# Amplifier.net
KiCad netlist of a schematic drawn in Altium Designer
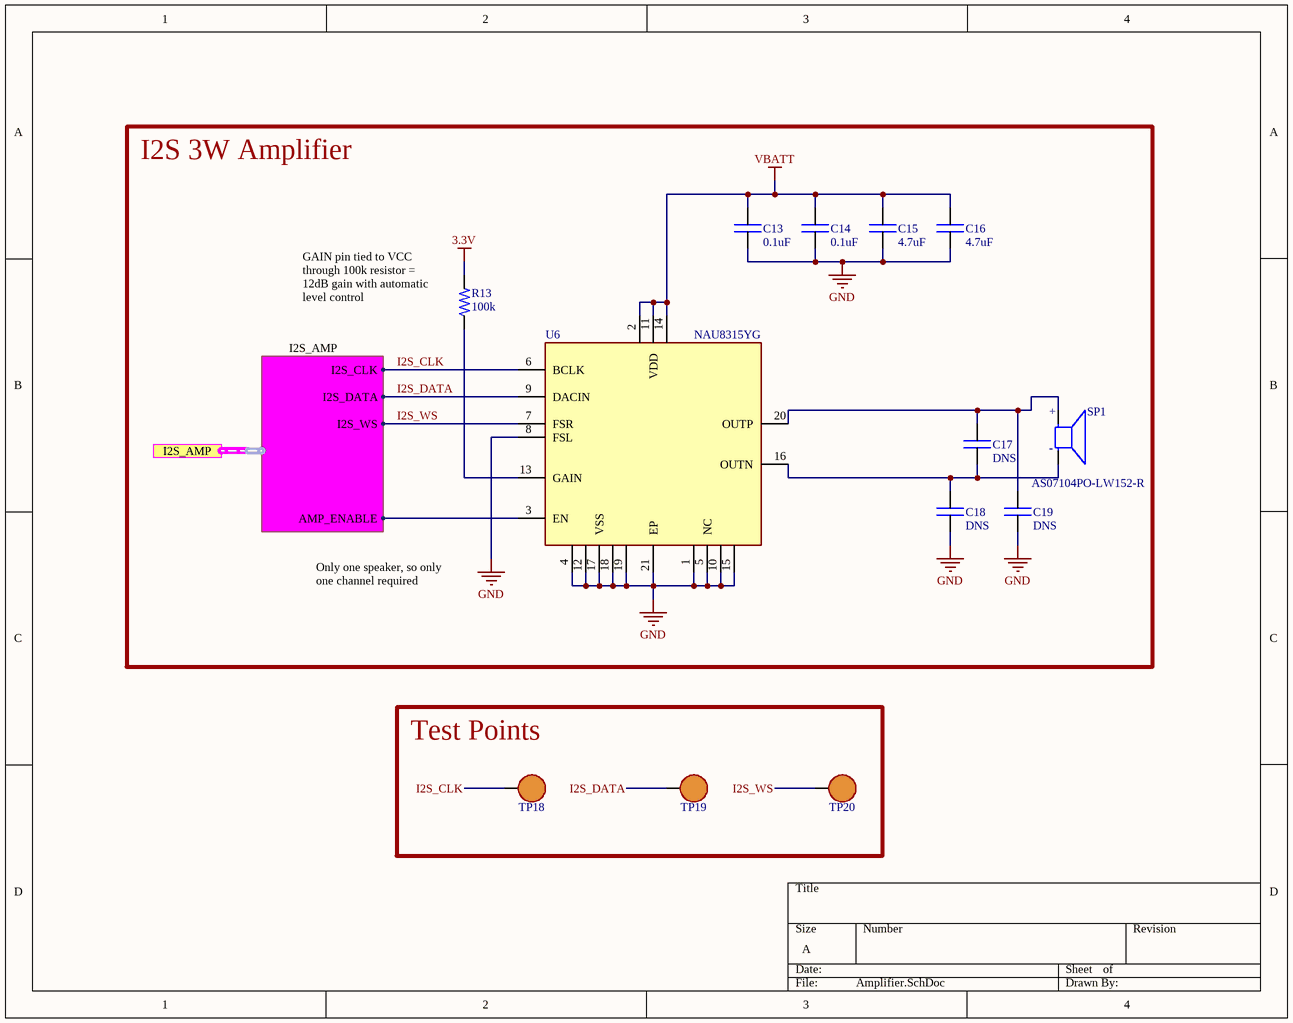
[diagram p0: Amplifier.SchDoc]

(export (version "E")
  (design (tool "Eeschema 10.0.6"))
  (components
    (comp (ref "C13")
      (value "0.1uF")
      (footprint "Christmas-2024_TSO-PCB:0402C")
      (description "Capacitor")
      (fields (field (name "MFR") "Samsung") (field (name "Comment") "CAP"))
      (libsource (lib "Christmas-2024_TSO-PCB") (part "CAP"))
    )
    (comp (ref "C14")
      (value "0.1uF")
      (footprint "Christmas-2024_TSO-PCB:0402C")
      (description "Capacitor")
      (fields (field (name "MFR") "Samsung") (field (name "Comment") "CAP"))
      (libsource (lib "Christmas-2024_TSO-PCB") (part "CAP"))
    )
    (comp (ref "C15")
      (value "4.7uF")
      (footprint "Christmas-2024_TSO-PCB:0402C")
      (description "Capacitor")
      (fields (field (name "MFR") "Samsung") (field (name "Comment") "CAP"))
      (libsource (lib "Christmas-2024_TSO-PCB") (part "CAP"))
    )
    (comp (ref "C16")
      (value "4.7uF")
      (footprint "Christmas-2024_TSO-PCB:0402C")
      (description "Capacitor")
      (fields (field (name "MFR") "Samsung") (field (name "Comment") "CAP"))
      (libsource (lib "Christmas-2024_TSO-PCB") (part "CAP"))
    )
    (comp (ref "C17")
      (value "DNS")
      (footprint "Christmas-2024_TSO-PCB:0402C")
      (description "Capacitor")
      (fields (field (name "Comment") "CAP"))
      (libsource (lib "Christmas-2024_TSO-PCB") (part "CAP"))
    )
    (comp (ref "C18")
      (value "DNS")
      (footprint "Christmas-2024_TSO-PCB:0402C")
      (description "Capacitor")
      (fields (field (name "Comment") "CAP"))
      (libsource (lib "Christmas-2024_TSO-PCB") (part "CAP"))
    )
    (comp (ref "C19")
      (value "DNS")
      (footprint "Christmas-2024_TSO-PCB:0402C")
      (description "Capacitor")
      (fields (field (name "Comment") "CAP"))
      (libsource (lib "Christmas-2024_TSO-PCB") (part "CAP"))
    )
    (comp (ref "R13")
      (value "100k")
      (footprint "Christmas-2024_TSO-PCB:0402R")
      (description "Resistor")
      (fields (field (name "MFR") "YAGEO") (field (name "Comment") "RES"))
      (libsource (lib "Christmas-2024_TSO-PCB") (part "RES"))
    )
    (comp (ref "SP1")
      (value "AS07104PO-LW152-R")
      (footprint "Christmas-2024_TSO-PCB:XMAS_26AWG_AS04004PO-2-LW152-R_SideMount")
      (description "SPEAKER 4OHM 3W TOP PORT 86DB")
      (fields (field (name "MFR") "PUI Audio, Inc."))
      (libsource (lib "Christmas-2024_TSO-PCB") (part "SPEAKER 4OHM 3W"))
    )
    (comp (ref "TP18")
      (value "RCWCTE")
      (footprint "Christmas-2024_TSO-PCB:RCWCTE")
      (description "Test Point, Surface Mount")
      (fields (field (name "MFR") "KOA Speer Electronics, Inc."))
      (libsource (lib "Christmas-2024_TSO-PCB") (part "TEST POINT"))
    )
    (comp (ref "TP19")
      (value "RCWCTE")
      (footprint "Christmas-2024_TSO-PCB:RCWCTE")
      (description "Test Point, Surface Mount")
      (fields (field (name "MFR") "KOA Speer Electronics, Inc."))
      (libsource (lib "Christmas-2024_TSO-PCB") (part "TEST POINT"))
    )
    (comp (ref "TP20")
      (value "RCWCTE")
      (footprint "Christmas-2024_TSO-PCB:RCWCTE")
      (description "Test Point, Surface Mount")
      (fields (field (name "MFR") "KOA Speer Electronics, Inc."))
      (libsource (lib "Christmas-2024_TSO-PCB") (part "TEST POINT"))
    )
    (comp (ref "U6")
      (value "NAU8315YG")
      (footprint "Christmas-2024_TSO-PCB:20-WFQFN-EP")
      (description "I2S MONO 3.2W CLASS-D AMPLIFIER")
      (fields (field (name "MFR") "Nuvoton"))
      (libsource (lib "Christmas-2024_TSO-PCB") (part "I2S 3W AMP"))
    )
  )
  (nets
    (net (code "2") (name "/AMP_ENABLE") (class "Default")
      (node (ref "U6") (pin "3") (pinfunction "EN_3") (pintype "passive"))
    )
    (net (code "3") (name "/I2S_CLK") (class "Default")
      (node (ref "TP18") (pin "1") (pinfunction "0_1") (pintype "passive"))
      (node (ref "U6") (pin "6") (pinfunction "BCLK_6") (pintype "passive"))
    )
    (net (code "4") (name "/I2S_DATA") (class "Default")
      (node (ref "TP19") (pin "1") (pinfunction "0_1") (pintype "passive"))
      (node (ref "U6") (pin "9") (pinfunction "DACIN_9") (pintype "passive"))
    )
    (net (code "5") (name "/I2S_WS") (class "Default")
      (node (ref "TP20") (pin "1") (pinfunction "0_1") (pintype "passive"))
      (node (ref "U6") (pin "7") (pinfunction "FSR_7") (pintype "passive"))
    )
    (net (code "7") (name "3.3V") (class "Default")
      (node (ref "R13") (pin "2") (pinfunction "2_2") (pintype "passive"))
    )
    (net (code "8") (name "GND") (class "Default")
      (node (ref "C13") (pin "1") (pinfunction "1_1") (pintype "passive"))
      (node (ref "C14") (pin "1") (pinfunction "1_1") (pintype "passive"))
      (node (ref "C15") (pin "1") (pinfunction "1_1") (pintype "passive"))
      (node (ref "C16") (pin "1") (pinfunction "1_1") (pintype "passive"))
      (node (ref "C18") (pin "1") (pinfunction "1_1") (pintype "passive"))
      (node (ref "C19") (pin "1") (pinfunction "1_1") (pintype "passive"))
      (node (ref "U6") (pin "1") (pinfunction "NC_1") (pintype "passive"))
      (node (ref "U6") (pin "10") (pinfunction "NC_10") (pintype "passive"))
      (node (ref "U6") (pin "12") (pinfunction "VSS_12") (pintype "passive"))
      (node (ref "U6") (pin "15") (pinfunction "NC_15") (pintype "passive"))
      (node (ref "U6") (pin "17") (pinfunction "VSS_17") (pintype "passive"))
      (node (ref "U6") (pin "18") (pinfunction "VSS_18") (pintype "passive"))
      (node (ref "U6") (pin "19") (pinfunction "VSS_19") (pintype "passive"))
      (node (ref "U6") (pin "21") (pinfunction "EP_21") (pintype "passive"))
      (node (ref "U6") (pin "4") (pinfunction "VSS_4") (pintype "passive"))
      (node (ref "U6") (pin "5") (pinfunction "NC_5") (pintype "passive"))
      (node (ref "U6") (pin "8") (pinfunction "FSL_8") (pintype "passive"))
    )
    (net (code "9") (name "Net-(U6-GAIN)") (class "Default")
      (node (ref "R13") (pin "1") (pinfunction "1_1") (pintype "passive"))
      (node (ref "U6") (pin "13") (pinfunction "GAIN_13") (pintype "passive"))
    )
    (net (code "10") (name "Net-(U6-OUTN)") (class "Default")
      (node (ref "C17") (pin "1") (pinfunction "1_1") (pintype "passive"))
      (node (ref "C18") (pin "2") (pinfunction "2_2") (pintype "passive"))
      (node (ref "SP1") (pin "N") (pinfunction "N_N") (pintype "passive"))
      (node (ref "U6") (pin "16") (pinfunction "OUTN_16") (pintype "passive"))
    )
    (net (code "11") (name "Net-(U6-OUTP)") (class "Default")
      (node (ref "C17") (pin "2") (pinfunction "2_2") (pintype "passive"))
      (node (ref "C19") (pin "2") (pinfunction "2_2") (pintype "passive"))
      (node (ref "SP1") (pin "P") (pinfunction "P_P") (pintype "passive"))
      (node (ref "U6") (pin "20") (pinfunction "OUTP_20") (pintype "passive"))
    )
    (net (code "12") (name "VBATT") (class "Default")
      (node (ref "C13") (pin "2") (pinfunction "2_2") (pintype "passive"))
      (node (ref "C14") (pin "2") (pinfunction "2_2") (pintype "passive"))
      (node (ref "C15") (pin "2") (pinfunction "2_2") (pintype "passive"))
      (node (ref "C16") (pin "2") (pinfunction "2_2") (pintype "passive"))
      (node (ref "U6") (pin "11") (pinfunction "VDD_11") (pintype "passive"))
      (node (ref "U6") (pin "14") (pinfunction "VDD_14") (pintype "passive"))
      (node (ref "U6") (pin "2") (pinfunction "VDD_2") (pintype "passive"))
    )
  )
)
